# switch-board.net
KiCad netlist of a schematic drawn in EAGLE
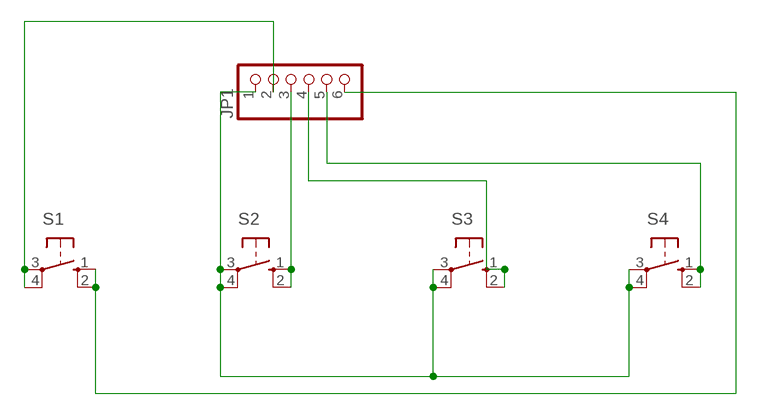
[diagram p0: schematic, sheet 1]

(export (version "E")
  (design (tool "Eeschema 10.0.6"))
  (components
    (comp (ref "JP1")
      (value "PINHD-1X6")
      (footprint "eagle-import:1X06")
      (libsource (lib "eagle-import") (part "PINHD-1X6"))
    )
    (comp (ref "S1")
      (value "10-XX")
      (footprint "eagle-import:B3F-10XX")
      (fields (field (name "MPN") "B3F-1000"))
      (libsource (lib "eagle-import") (part "10-XX"))
    )
    (comp (ref "S2")
      (value "10-XX")
      (footprint "eagle-import:B3F-10XX")
      (fields (field (name "MPN") "B3F-1000"))
      (libsource (lib "eagle-import") (part "10-XX"))
    )
    (comp (ref "S3")
      (value "10-XX")
      (footprint "eagle-import:B3F-10XX")
      (fields (field (name "MPN") "B3F-1000"))
      (libsource (lib "eagle-import") (part "10-XX"))
    )
    (comp (ref "S4")
      (value "10-XX")
      (footprint "eagle-import:B3F-10XX")
      (fields (field (name "MPN") "B3F-1000"))
      (libsource (lib "eagle-import") (part "10-XX"))
    )
  )
  (nets
    (net (code "1") (name "Net-(S1-P)") (class "Default")
      (node (ref "JP1") (pin "2") (pinfunction "2_2") (pintype "passive"))
      (node (ref "S1") (pin "3") (pinfunction "P_3") (pintype "passive"))
      (node (ref "S1") (pin "4") (pinfunction "P1_4") (pintype "passive"))
    )
    (net (code "2") (name "Net-(S1-S)") (class "Default")
      (node (ref "JP1") (pin "6") (pinfunction "6_6") (pintype "passive"))
      (node (ref "S1") (pin "1") (pinfunction "S_1") (pintype "passive"))
      (node (ref "S1") (pin "2") (pinfunction "S1_2") (pintype "passive"))
    )
    (net (code "3") (name "Net-(S2-P)") (class "Default")
      (node (ref "JP1") (pin "1") (pinfunction "1_1") (pintype "passive"))
      (node (ref "S2") (pin "3") (pinfunction "P_3") (pintype "passive"))
      (node (ref "S2") (pin "4") (pinfunction "P1_4") (pintype "passive"))
      (node (ref "S3") (pin "3") (pinfunction "P_3") (pintype "passive"))
      (node (ref "S3") (pin "4") (pinfunction "P1_4") (pintype "passive"))
      (node (ref "S4") (pin "3") (pinfunction "P_3") (pintype "passive"))
      (node (ref "S4") (pin "4") (pinfunction "P1_4") (pintype "passive"))
    )
    (net (code "4") (name "Net-(S2-S)") (class "Default")
      (node (ref "JP1") (pin "3") (pinfunction "3_3") (pintype "passive"))
      (node (ref "S2") (pin "1") (pinfunction "S_1") (pintype "passive"))
      (node (ref "S2") (pin "2") (pinfunction "S1_2") (pintype "passive"))
    )
    (net (code "5") (name "Net-(S3-S)") (class "Default")
      (node (ref "JP1") (pin "4") (pinfunction "4_4") (pintype "passive"))
      (node (ref "S3") (pin "1") (pinfunction "S_1") (pintype "passive"))
      (node (ref "S3") (pin "2") (pinfunction "S1_2") (pintype "passive"))
    )
    (net (code "6") (name "Net-(S4-S)") (class "Default")
      (node (ref "JP1") (pin "5") (pinfunction "5_5") (pintype "passive"))
      (node (ref "S4") (pin "1") (pinfunction "S_1") (pintype "passive"))
      (node (ref "S4") (pin "2") (pinfunction "S1_2") (pintype "passive"))
    )
  )
)
